# 1u_panel.net
KiCad netlist of a schematic drawn in EAGLE
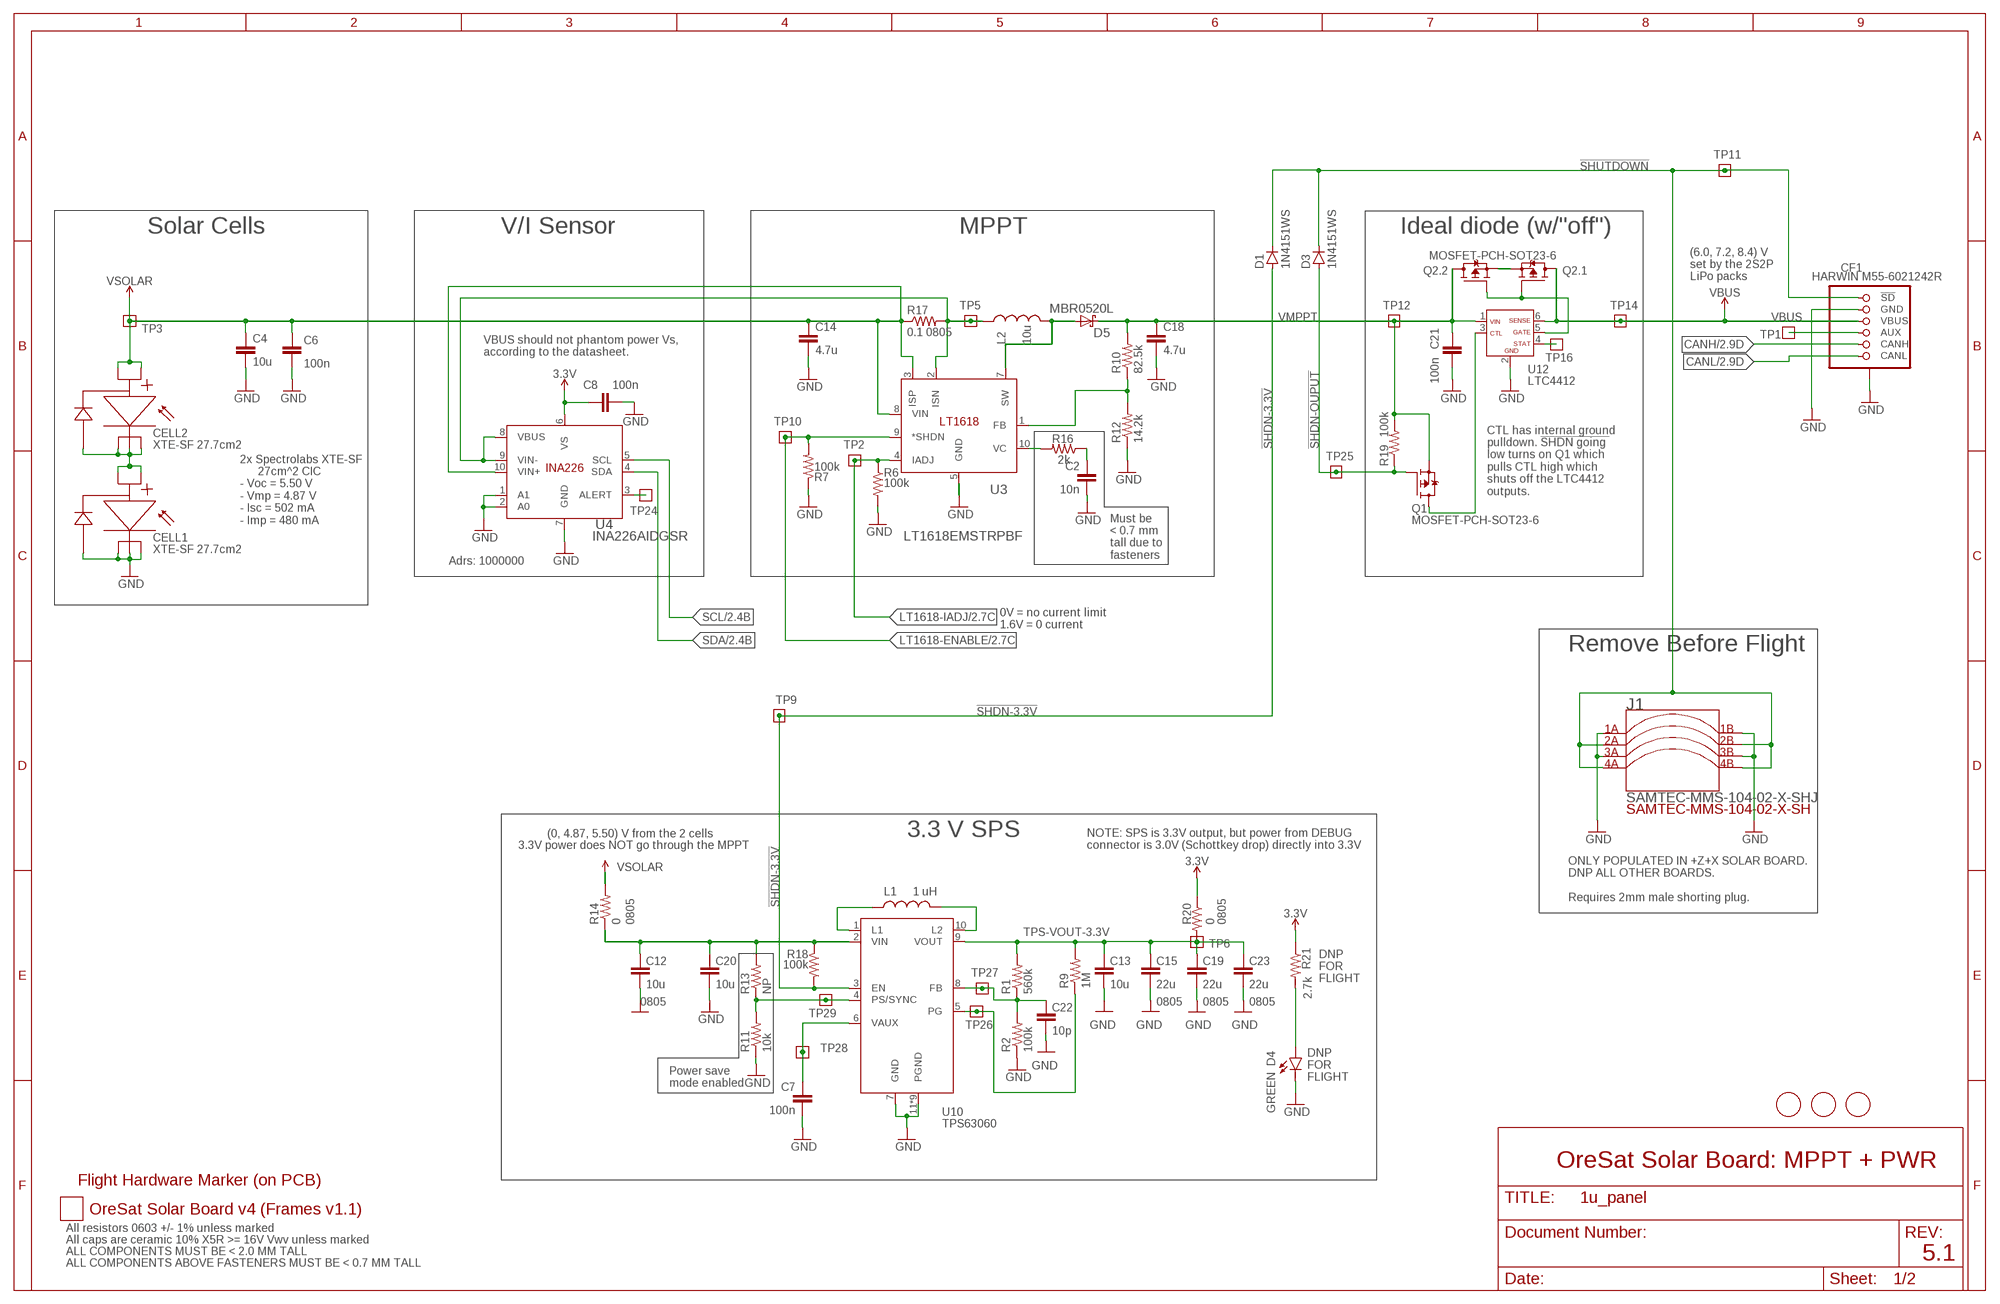
[diagram p0: schematic, sheet 1]
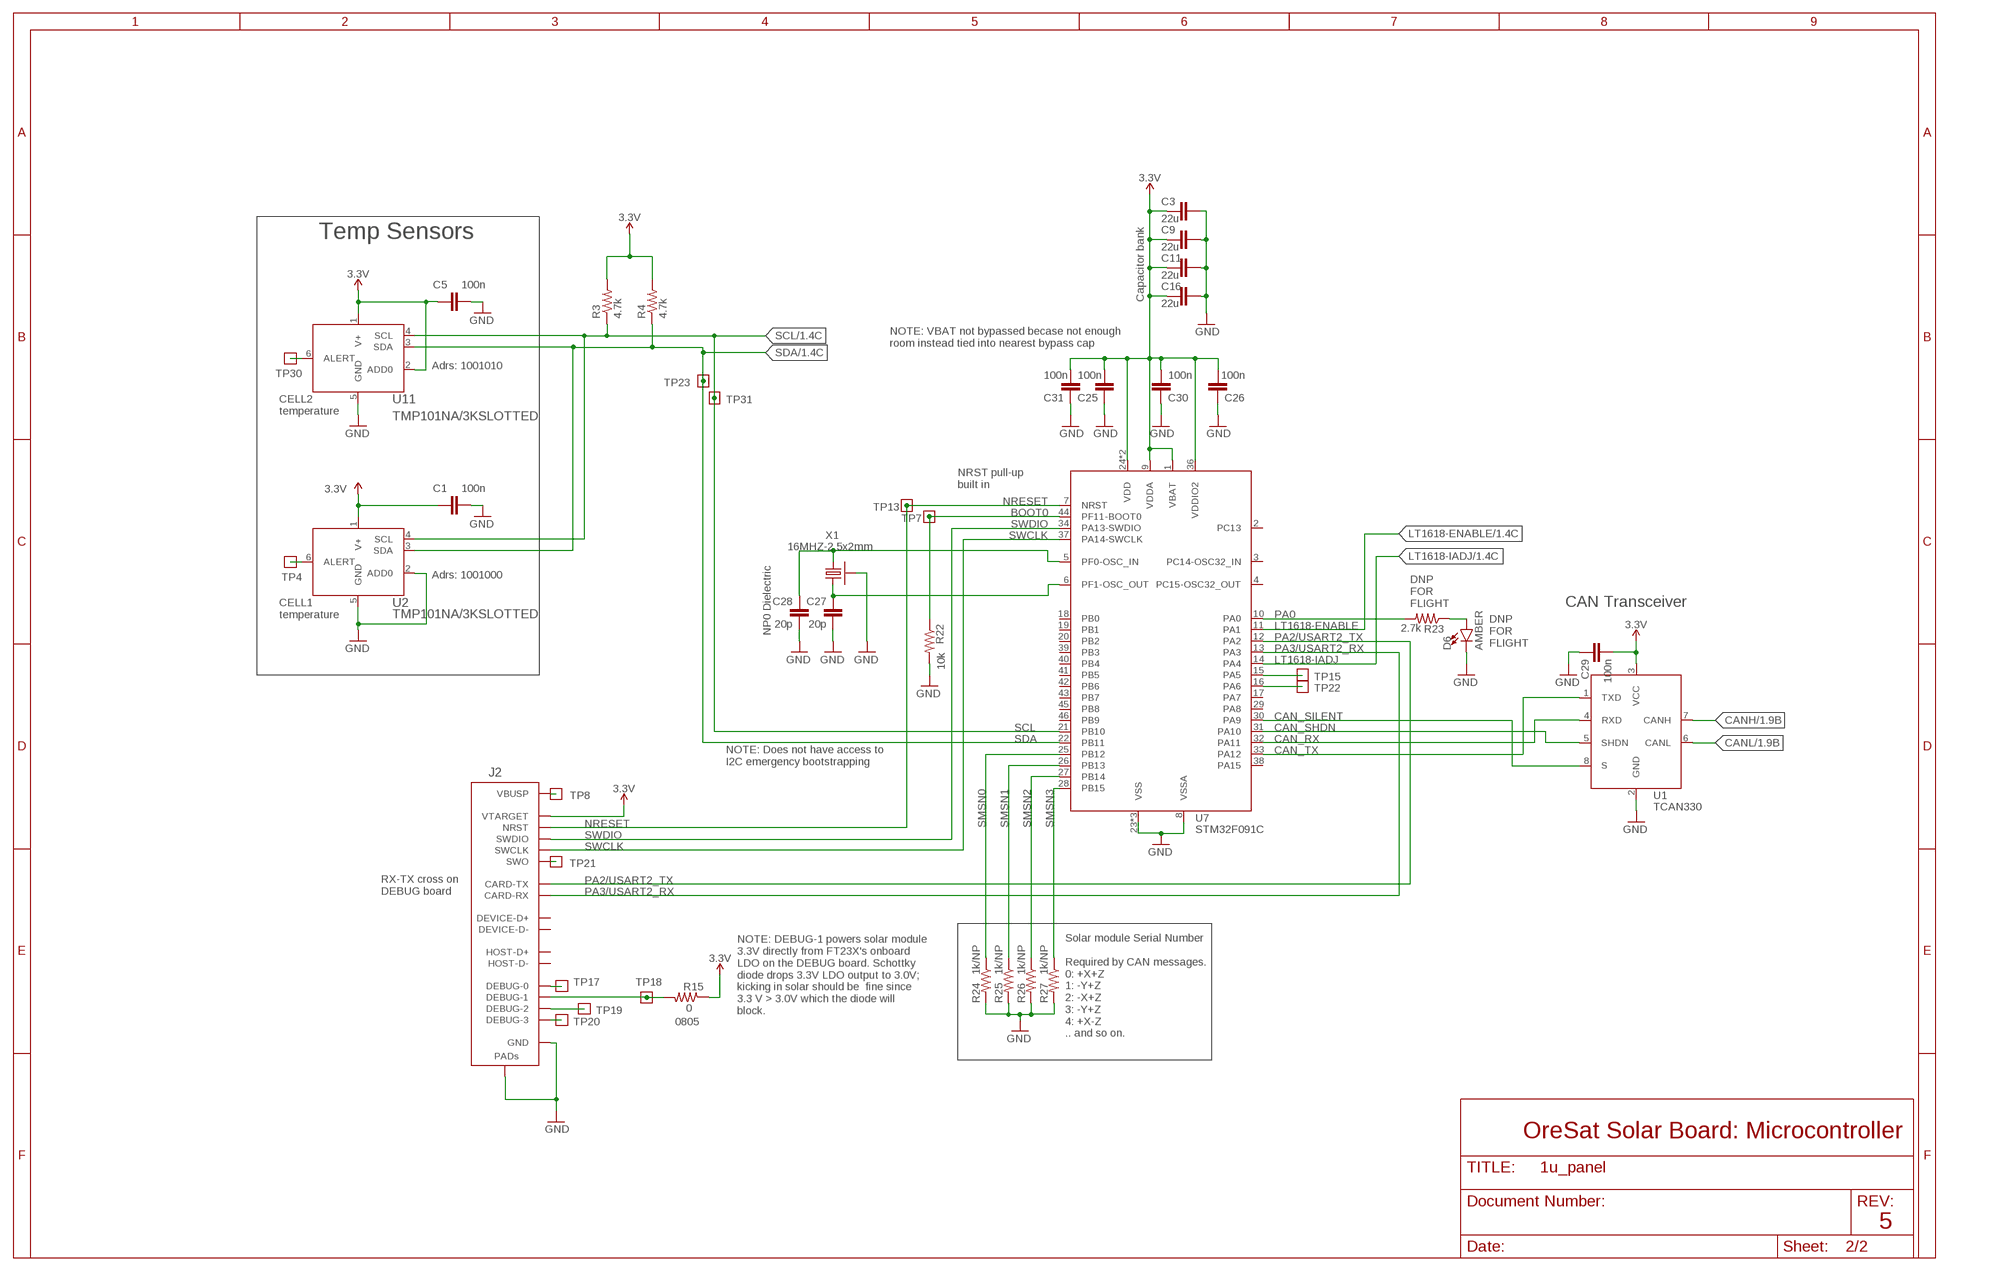
[diagram p1: schematic, sheet 2]

(export (version "E")
  (design (tool "Eeschema 10.0.6"))
  (components
    (comp (ref "C1")
      (value "100n")
      (footprint "eagle-import:.0603-C-NOSILK")
      (fields (field (name "MFR") "Kemet") (field (name "MPN") "CL10B104KB85PND"))
      (libsource (lib "eagle-import") (part "C-EU0603-C-NOSILK"))
    )
    (comp (ref "C3")
      (value "22u")
      (footprint "eagle-import:.0805-B-NOSILK")
      (fields (field (name "MFR") "Samsung") (field (name "MPN") "CL32B226KOJVPNE"))
      (libsource (lib "eagle-import") (part "C-EU0805-B-NOSILK"))
    )
    (comp (ref "C5")
      (value "100n")
      (footprint "eagle-import:.0603-C-NOSILK")
      (fields (field (name "MFR") "Kemet") (field (name "MPN") "CL10B104KB85PND"))
      (libsource (lib "eagle-import") (part "C-EU0603-C-NOSILK"))
    )
    (comp (ref "C9")
      (value "22u")
      (footprint "eagle-import:.0805-B-NOSILK")
      (fields (field (name "MFR") "Samsung") (field (name "MPN") "CL32B226KOJVPNE"))
      (libsource (lib "eagle-import") (part "C-EU0805-B-NOSILK"))
    )
    (comp (ref "C11")
      (value "22u")
      (footprint "eagle-import:.0805-B-NOSILK")
      (fields (field (name "MFR") "Samsung") (field (name "MPN") "CL32B226KOJVPNE"))
      (libsource (lib "eagle-import") (part "C-EU0805-B-NOSILK"))
    )
    (comp (ref "C16")
      (value "22u")
      (footprint "eagle-import:.0805-B-NOSILK")
      (fields (field (name "MFR") "Samsung") (field (name "MPN") "CL32B226KOJVPNE"))
      (libsource (lib "eagle-import") (part "C-EU0805-B-NOSILK"))
    )
    (comp (ref "C25")
      (value "100n")
      (footprint "eagle-import:.0603-C-NOSILK")
      (fields (field (name "MFR") "Kemet") (field (name "MPN") "CL10B104KB85PND"))
      (libsource (lib "eagle-import") (part "C-EU0603-C-NOSILK"))
    )
    (comp (ref "C26")
      (value "100n")
      (footprint "eagle-import:.0603-C-NOSILK")
      (fields (field (name "MFR") "Kemet") (field (name "MPN") "CL10B104KB85PND"))
      (libsource (lib "eagle-import") (part "C-EU0603-C-NOSILK"))
    )
    (comp (ref "C27")
      (value "20p")
      (footprint "eagle-import:.0603-C-NOSILK")
      (fields (field (name "MFR") "Murata") (field (name "MPN") "GCM1885C2A200JA16D"))
      (libsource (lib "eagle-import") (part "C-EU0603-C-NOSILK"))
    )
    (comp (ref "C28")
      (value "20p")
      (footprint "eagle-import:.0603-C-NOSILK")
      (fields (field (name "MFR") "Murata") (field (name "MPN") "GCM1885C2A200JA16D"))
      (libsource (lib "eagle-import") (part "C-EU0603-C-NOSILK"))
    )
    (comp (ref "C29")
      (value "100n")
      (footprint "eagle-import:.0603-C-NOSILK")
      (fields (field (name "MFR") "Kemet") (field (name "MPN") "CL10B104KB85PND"))
      (libsource (lib "eagle-import") (part "C-EU0603-C-NOSILK"))
    )
    (comp (ref "C30")
      (value "100n")
      (footprint "eagle-import:.0603-C-NOSILK")
      (fields (field (name "MFR") "Kemet") (field (name "MPN") "CL10B104KB85PND"))
      (libsource (lib "eagle-import") (part "C-EU0603-C-NOSILK"))
    )
    (comp (ref "C31")
      (value "100n")
      (footprint "eagle-import:.0603-C-NOSILK")
      (fields (field (name "MFR") "Kemet") (field (name "MPN") "CL10B104KB85PND"))
      (libsource (lib "eagle-import") (part "C-EU0603-C-NOSILK"))
    )
    (comp (ref "D6")
      (value "AMBER")
      (footprint "eagle-import:LED-0603")
      (fields (field (name "MFR") "Inolux") (field (name "MPN") "IN-S63AT5A"))
      (libsource (lib "eagle-import") (part "LED-GREEN0603"))
    )
    (comp (ref "J2")
      (value "ORESAT-DEBUG-CONNECTOR-ALL")
      (footprint "eagle-import:TE_2-1734592-0")
      (fields (field (name "MFR") "Wurth") (field (name "MPN") "687120183622  "))
      (libsource (lib "eagle-import") (part "ORESAT-DEBUG-CONNECTOR-ALL"))
    )
    (comp (ref "R3")
      (value "4.7k")
      (footprint "eagle-import:.0603-C-NOSILK")
      (fields (field (name "MFR") "Yageo") (field (name "MPN") "RE0603FRE074K7L"))
      (libsource (lib "eagle-import") (part "R-US_0603-C-NOSILK"))
    )
    (comp (ref "R4")
      (value "4.7k")
      (footprint "eagle-import:.0603-C-NOSILK")
      (fields (field (name "MFR") "Yageo") (field (name "MPN") "RE0603FRE074K7L"))
      (libsource (lib "eagle-import") (part "R-US_0603-C-NOSILK"))
    )
    (comp (ref "R15")
      (value "0")
      (footprint "eagle-import:.0805-C-NOSILK")
      (fields (field (name "MFR") "Stackpole") (field (name "MPN") "RMCF0805ZT0R00"))
      (libsource (lib "eagle-import") (part "R-US_0805-C-NOSILK"))
    )
    (comp (ref "R22")
      (value "10k")
      (footprint "eagle-import:.0603-C-NOSILK")
      (fields (field (name "MFR") "TE") (field (name "MPN") "CRGCQ0603F2K7"))
      (libsource (lib "eagle-import") (part "R-US_0603-C-NOSILK"))
    )
    (comp (ref "R23")
      (value "2.7k")
      (footprint "eagle-import:.0603-C-NOSILK")
      (fields (field (name "MFR") "TE") (field (name "MPN") "CRGCQ0603F2K7"))
      (libsource (lib "eagle-import") (part "R-US_0603-C-NOSILK"))
    )
    (comp (ref "R24")
      (value "1k/NP")
      (footprint "eagle-import:.0603-C-NOSILK")
      (fields (field (name "MFR") "Bourns") (field (name "MPN") "CR0603AFX-1001ELF"))
      (libsource (lib "eagle-import") (part "R-US_0603-C-NOSILK"))
    )
    (comp (ref "R25")
      (value "1k/NP")
      (footprint "eagle-import:.0603-C-NOSILK")
      (fields (field (name "MFR") "Bourns") (field (name "MPN") "CR0603AFX-1001ELF"))
      (libsource (lib "eagle-import") (part "R-US_0603-C-NOSILK"))
    )
    (comp (ref "R26")
      (value "1k/NP")
      (footprint "eagle-import:.0603-C-NOSILK")
      (fields (field (name "MFR") "Bourns") (field (name "MPN") "CR0603AFX-1001ELF"))
      (libsource (lib "eagle-import") (part "R-US_0603-C-NOSILK"))
    )
    (comp (ref "R27")
      (value "1k/NP")
      (footprint "eagle-import:.0603-C-NOSILK")
      (fields (field (name "MFR") "Bourns") (field (name "MPN") "CR0603AFX-1001ELF"))
      (libsource (lib "eagle-import") (part "R-US_0603-C-NOSILK"))
    )
    (comp (ref "TP4")
      (value "TEST-POINT-LARGE-SQUARE")
      (footprint "eagle-import:1X01")
      (libsource (lib "eagle-import") (part "TEST-POINT-LARGE-SQUARE"))
    )
    (comp (ref "TP7")
      (value "TEST-POINT-LARGE-SQUARE")
      (footprint "eagle-import:1X01")
      (libsource (lib "eagle-import") (part "TEST-POINT-LARGE-SQUARE"))
    )
    (comp (ref "TP8")
      (value "TEST-POINT-LARGE-SQUARE")
      (footprint "eagle-import:1X01")
      (libsource (lib "eagle-import") (part "TEST-POINT-LARGE-SQUARE"))
    )
    (comp (ref "TP13")
      (value "TEST-POINT-LARGE-SQUARE")
      (footprint "eagle-import:1X01")
      (libsource (lib "eagle-import") (part "TEST-POINT-LARGE-SQUARE"))
    )
    (comp (ref "TP15")
      (value "TEST-POINT-LARGE-SQUARE")
      (footprint "eagle-import:1X01")
      (libsource (lib "eagle-import") (part "TEST-POINT-LARGE-SQUARE"))
    )
    (comp (ref "TP17")
      (value "TEST-POINT-LARGE-SQUARE")
      (footprint "eagle-import:1X01")
      (libsource (lib "eagle-import") (part "TEST-POINT-LARGE-SQUARE"))
    )
    (comp (ref "TP18")
      (value "TEST-POINT-LARGE-SQUARE")
      (footprint "eagle-import:1X01")
      (libsource (lib "eagle-import") (part "TEST-POINT-LARGE-SQUARE"))
    )
    (comp (ref "TP19")
      (value "TEST-POINT-LARGE-SQUARE")
      (footprint "eagle-import:1X01")
      (libsource (lib "eagle-import") (part "TEST-POINT-LARGE-SQUARE"))
    )
    (comp (ref "TP20")
      (value "TEST-POINT-LARGE-SQUARE")
      (footprint "eagle-import:1X01")
      (libsource (lib "eagle-import") (part "TEST-POINT-LARGE-SQUARE"))
    )
    (comp (ref "TP21")
      (value "TEST-POINT-LARGE-SQUARE")
      (footprint "eagle-import:1X01")
      (libsource (lib "eagle-import") (part "TEST-POINT-LARGE-SQUARE"))
    )
    (comp (ref "TP22")
      (value "TEST-POINT-LARGE-SQUARE")
      (footprint "eagle-import:1X01")
      (libsource (lib "eagle-import") (part "TEST-POINT-LARGE-SQUARE"))
    )
    (comp (ref "TP23")
      (value "TEST-POINT-LARGE-SQUARE")
      (footprint "eagle-import:1X01")
      (libsource (lib "eagle-import") (part "TEST-POINT-LARGE-SQUARE"))
    )
    (comp (ref "TP30")
      (value "TEST-POINT-LARGE-SQUARE")
      (footprint "eagle-import:1X01")
      (libsource (lib "eagle-import") (part "TEST-POINT-LARGE-SQUARE"))
    )
    (comp (ref "TP31")
      (value "TEST-POINT-LARGE-SQUARE")
      (footprint "eagle-import:1X01")
      (libsource (lib "eagle-import") (part "TEST-POINT-LARGE-SQUARE"))
    )
    (comp (ref "U1")
      (value "TCAN330")
      (footprint "eagle-import:SOT23-8_TI-DCN")
      (fields (field (name "MFR") "Texas Instruments") (field (name "MPN") "TCAN330GDCNT"))
      (libsource (lib "eagle-import") (part "TCAN330"))
    )
    (comp (ref "U2")
      (value "TMP101NA/3KSLOTTED")
      (footprint "eagle-import:DBV6-SLOT")
      (fields (field (name "MFR") "Texas Instruments") (field (name "MPN") "TMP101NA/3K"))
      (libsource (lib "eagle-import") (part "TMP101NA/3KSLOTTED"))
    )
    (comp (ref "U7")
      (value "STM32F091C")
      (footprint "eagle-import:STM32F091C")
      (fields (field (name "MFR") "STMicroelectronics") (field (name "MPN") "STM32F091CCT6TR"))
      (libsource (lib "eagle-import") (part "STM32F091C"))
    )
    (comp (ref "U11")
      (value "TMP101NA/3KSLOTTED")
      (footprint "eagle-import:DBV6-SLOT")
      (fields (field (name "MFR") "Texas Instruments") (field (name "MPN") "TMP101NA/3K"))
      (libsource (lib "eagle-import") (part "TMP101NA/3KSLOTTED"))
    )
    (comp (ref "X1")
      (value "16MHZ-2.5x2mm")
      (footprint "eagle-import:CRYSTAL_2.5X2")
      (fields (field (name "MFR") "ECS Inc.") (field (name "MPN") "ECS-160-10-36Q-ES-TR"))
      (libsource (lib "eagle-import") (part "CRYSTAL-WITH-GND"))
    )
    (comp (ref "C2")
      (value "10n")
      (footprint "eagle-import:.0603-C-NOSILK")
      (fields (field (name "MFR") "Taiyo") (field (name "MPN") "UMK107B7103KAHT"))
      (libsource (lib "eagle-import") (part "C-EU0603-C-NOSILK"))
    )
    (comp (ref "C4")
      (value "10u")
      (footprint "eagle-import:.0603-C-NOSILK")
      (fields (field (name "MFR") "Murata") (field (name "MPN") "GRT188R61C106KE13D"))
      (libsource (lib "eagle-import") (part "C-EU0603-C-NOSILK"))
    )
    (comp (ref "C6")
      (value "100n")
      (footprint "eagle-import:.0603-C-NOSILK")
      (fields (field (name "MFR") "Kemet") (field (name "MPN") "CL10B104KB85PND"))
      (libsource (lib "eagle-import") (part "C-EU0603-C-NOSILK"))
    )
    (comp (ref "C7")
      (value "100n")
      (footprint "eagle-import:.0603-C-NOSILK")
      (fields (field (name "MFR") "Kemet") (field (name "MPN") "CL10B104KB85PND"))
      (libsource (lib "eagle-import") (part "C-EU0603-C-NOSILK"))
    )
    (comp (ref "C8")
      (value "100n")
      (footprint "eagle-import:.0603-C-NOSILK")
      (fields (field (name "MFR") "Kemet") (field (name "MPN") "CL10B104KB85PND"))
      (libsource (lib "eagle-import") (part "C-EU0603-C-NOSILK"))
    )
    (comp (ref "C12")
      (value "10u")
      (footprint "eagle-import:.0805-B-NOSILK")
      (fields (field (name "MFR") "Murata") (field (name "MPN") "GRT21BR61C106KE01L"))
      (libsource (lib "eagle-import") (part "C-EU0805-B-NOSILK"))
    )
    (comp (ref "C13")
      (value "10u")
      (footprint "eagle-import:.0603-C-NOSILK")
      (fields (field (name "MFR") "Murata") (field (name "MPN") "GRT188R61C106KE13D"))
      (libsource (lib "eagle-import") (part "C-EU0603-C-NOSILK"))
    )
    (comp (ref "C14")
      (value "4.7u")
      (footprint "eagle-import:.0603-C-NOSILK")
      (fields (field (name "MFR") "Taiyo") (field (name "MPN") "EMK107BBJ475KAHT"))
      (libsource (lib "eagle-import") (part "C-EU0603-C-NOSILK"))
    )
    (comp (ref "C15")
      (value "22u")
      (footprint "eagle-import:.0805-B-NOSILK")
      (fields (field (name "MFR") "Samsung") (field (name "MPN") "CL32B226KOJVPNE"))
      (libsource (lib "eagle-import") (part "C-EU0805-B-NOSILK"))
    )
    (comp (ref "C18")
      (value "4.7u")
      (footprint "eagle-import:.0603-C-NOSILK")
      (fields (field (name "MFR") "Taiyo") (field (name "MPN") "EMK107BBJ475KAHT"))
      (libsource (lib "eagle-import") (part "C-EU0603-C-NOSILK"))
    )
    (comp (ref "C19")
      (value "22u")
      (footprint "eagle-import:.0805-B-NOSILK")
      (fields (field (name "MFR") "Samsung") (field (name "MPN") "CL32B226KOJVPNE"))
      (libsource (lib "eagle-import") (part "C-EU0805-B-NOSILK"))
    )
    (comp (ref "C20")
      (value "10u")
      (footprint "eagle-import:.0603-C-NOSILK")
      (fields (field (name "MFR") "Murata") (field (name "MPN") "GRT188R61C106KE13D"))
      (libsource (lib "eagle-import") (part "C-EU0603-C-NOSILK"))
    )
    (comp (ref "C21")
      (value "100n")
      (footprint "eagle-import:.0402-B-NOSILK")
      (fields (field (name "MFR") "Kemet") (field (name "MPN") "CL10B104KB85PND"))
      (libsource (lib "eagle-import") (part "rcl_custom_C-EU0402-B-NOSILK"))
    )
    (comp (ref "C22")
      (value "10p")
      (footprint "eagle-import:.0603-C-NOSILK")
      (fields (field (name "MFR") "Murata") (field (name "MPN") "GRT188R61C106KE13D"))
      (libsource (lib "eagle-import") (part "C-EU0603-C-NOSILK"))
    )
    (comp (ref "C23")
      (value "22u")
      (footprint "eagle-import:.0805-B-NOSILK")
      (fields (field (name "MFR") "Samsung") (field (name "MPN") "CL32B226KOJVPNE"))
      (libsource (lib "eagle-import") (part "C-EU0805-B-NOSILK"))
    )
    (comp (ref "CELL1")
      (value "XTE-SF 27.7cm2")
      (footprint "eagle-import:SPECTROLAB-XTE-SF")
      (libsource (lib "eagle-import") (part "SPECTROLAB-XTE-SF"))
    )
    (comp (ref "CELL2")
      (value "XTE-SF 27.7cm2")
      (footprint "eagle-import:SPECTROLAB-XTE-SF")
      (libsource (lib "eagle-import") (part "SPECTROLAB-XTE-SF"))
    )
    (comp (ref "CF1")
      (value "HARWIN M55-6021242R")
      (footprint "eagle-import:HARWIN-M55-60X1242R")
      (fields (field (name "MFR") "HARWIN") (field (name "MPN") "M55-6021242R"))
      (libsource (lib "eagle-import") (part "SOLAR-BOARD-CONNECTOR"))
    )
    (comp (ref "D1")
      (value "1N4151WS")
      (footprint "eagle-import:SOD323-R")
      (libsource (lib "eagle-import") (part "DIODE-SOD323-R"))
    )
    (comp (ref "D3")
      (value "1N4151WS")
      (footprint "eagle-import:SOD323-R")
      (libsource (lib "eagle-import") (part "DIODE-SOD323-R"))
    )
    (comp (ref "D4")
      (value "GREEN")
      (footprint "eagle-import:LED-0603")
      (fields (field (name "MFR") "Inolux") (field (name "MPN") "IN-S63AT5A"))
      (libsource (lib "eagle-import") (part "LED-GREEN0603"))
    )
    (comp (ref "D5")
      (value "MBR0520L")
      (footprint "eagle-import:SOD123")
      (fields (field (name "MFR") "OnSemi") (field (name "MPN") "NRVB130T3G"))
      (libsource (lib "eagle-import") (part "NRVB130TGSOD123"))
    )
    (comp (ref "J1")
      (value "SAMTEC-MMS-104-02-X-SHJ")
      (footprint "eagle-import:SAMTEC-MMS-104-02-X-SH")
      (libsource (lib "eagle-import") (part "SAMTEC-MMS-104-02-X-SHJ"))
    )
    (comp (ref "L1")
      (value "1 uH")
      (footprint "eagle-import:IND_1226AS-H-1R0N=P2")
      (fields (field (name "MFR") "TDK") (field (name "MPN") "VLS3010CX-1R5M-1"))
      (libsource (lib "eagle-import") (part "L-MURATA-1226AS-H-1R0N=P2"))
    )
    (comp (ref "L2")
      (value "10u")
      (footprint "eagle-import:NONSTANDARD")
      (fields (field (name "MFR") "WURTH") (field (name "MPN") "744042100"))
      (libsource (lib "eagle-import") (part "L-WURTH-744042100"))
    )
    (comp (ref "PCB1")
      (value "ORESAT-SOLAR-BOARD-V4-SPECTROLABS")
      (footprint "eagle-import:ORESAT-SOLAR-BOARD-V4")
      (libsource (lib "eagle-import") (part "ORESAT-SOLAR-BOARD-V4-SPECTROLABS"))
    )
    (comp (ref "Q1")
      (value "MOSFET-PCH-SOT23-6")
      (footprint "eagle-import:SOT23-6")
      (fields (field (name "MFR") "Diodes Inc.") (field (name "MPN") "DMP3050LVT-7"))
      (libsource (lib "eagle-import") (part "MOSFET-PCH-SOT23-6"))
    )
    (comp (ref "Q2")
      (value "MOSFET-PCH-SOT23-6")
      (footprint "eagle-import:SOT23-6")
      (fields
        (field (name "MFR") "Diodes Inc.")
        (field (name "MPN") "DMP2240UDM-7")
        (field (name "DIS") "Digi-Key")
        (field (name "DPN") "DMP2240UDMDICT-ND")
      )
      (libsource (lib "eagle-import") (part "Q-MOSFET-PCH-dual-SOT23-6_MOSFET-PCH-SOT23-6"))
    )
    (comp (ref "R1")
      (value "560k")
      (footprint "eagle-import:.0603-C-NOSILK")
      (fields (field (name "MFR") "TE") (field (name "MPN") "CRGCQ0603F470K"))
      (libsource (lib "eagle-import") (part "R-US_0603-C-NOSILK"))
    )
    (comp (ref "R2")
      (value "100k")
      (footprint "eagle-import:.0603-C-NOSILK")
      (fields (field (name "MFR") "Susumu") (field (name "MPN") "RR0816P-104-D"))
      (libsource (lib "eagle-import") (part "R-US_0603-C-NOSILK"))
    )
    (comp (ref "R6")
      (value "100k")
      (footprint "eagle-import:.0603-C-NOSILK")
      (fields (field (name "MFR") "Stackpole") (field (name "MPN") "RNCP0603FTD10K0"))
      (libsource (lib "eagle-import") (part "R-US_0603-C-NOSILK"))
    )
    (comp (ref "R7")
      (value "100k")
      (footprint "eagle-import:.0603-C-NOSILK")
      (fields (field (name "MFR") "Stackpole") (field (name "MPN") "RNCP0603FTD10K0"))
      (libsource (lib "eagle-import") (part "R-US_0603-C-NOSILK"))
    )
    (comp (ref "R9")
      (value "1M")
      (footprint "eagle-import:.0603-C-NOSILK")
      (libsource (lib "eagle-import") (part "R-US_0603-C-NOSILK"))
    )
    (comp (ref "R10")
      (value "82.5k")
      (footprint "eagle-import:.0603-C-NOSILK")
      (fields (field (name "MFR") "Panasonic") (field (name "MPN") "ERA-3AEB8252V"))
      (libsource (lib "eagle-import") (part "R-US_0603-C-NOSILK"))
    )
    (comp (ref "R11")
      (value "10k")
      (footprint "eagle-import:.0603-C-NOSILK")
      (libsource (lib "eagle-import") (part "R-US_0603-C-NOSILK"))
    )
    (comp (ref "R12")
      (value "14.2k")
      (footprint "eagle-import:.0603-C-NOSILK")
      (fields (field (name "MFR") "KOA") (field (name "MPN") "RN73R1JTTD1422D25"))
      (libsource (lib "eagle-import") (part "R-US_0603-C-NOSILK"))
    )
    (comp (ref "R13")
      (value "NP")
      (footprint "eagle-import:.0603-C-NOSILK")
      (fields (field (name "MFR") "Stackpole") (field (name "MPN") "RNCP0603FTD10K0"))
      (libsource (lib "eagle-import") (part "R-US_0603-C-NOSILK"))
    )
    (comp (ref "R14")
      (value "0")
      (footprint "eagle-import:.0805-C-NOSILK")
      (fields (field (name "MFR") "Stackpole") (field (name "MPN") "RMCF0805ZT0R00"))
      (libsource (lib "eagle-import") (part "R-US_0805-C-NOSILK"))
    )
    (comp (ref "R16")
      (value "2k")
      (footprint "eagle-import:.0603-C-NOSILK")
      (fields (field (name "MFR") "KOA") (field (name "MPN") "RK73H1JTTD2001F"))
      (libsource (lib "eagle-import") (part "R-US_0603-C-NOSILK"))
    )
    (comp (ref "R17")
      (value "0.1 0805")
      (footprint "eagle-import:.0805-C-NOSILK")
      (fields (field (name "MFR") "Stackpole") (field (name "MPN") "RMCF0805ZT0R00"))
      (libsource (lib "eagle-import") (part "R-US_0805-C-NOSILK"))
    )
    (comp (ref "R18")
      (value "100k")
      (footprint "eagle-import:.0603-C-NOSILK")
      (fields (field (name "MFR") "Stackpole") (field (name "MPN") "RNCP0603FTD10K0"))
      (libsource (lib "eagle-import") (part "R-US_0603-C-NOSILK"))
    )
    (comp (ref "R19")
      (value "100k")
      (footprint "eagle-import:.0603-C-NOSILK")
      (fields (field (name "MFR") "Stackpole") (field (name "MPN") "RNCP0603FTD10K0"))
      (libsource (lib "eagle-import") (part "R-US_0603-C-NOSILK"))
    )
    (comp (ref "R20")
      (value "0")
      (footprint "eagle-import:.0805-C-NOSILK")
      (fields (field (name "MFR") "Stackpole") (field (name "MPN") "RMCF0805ZT0R00"))
      (libsource (lib "eagle-import") (part "R-US_0805-C-NOSILK"))
    )
    (comp (ref "R21")
      (value "2.7k")
      (footprint "eagle-import:.0603-C-NOSILK")
      (fields (field (name "MFR") "TE") (field (name "MPN") "CRGCQ0603F2K7"))
      (libsource (lib "eagle-import") (part "R-US_0603-C-NOSILK"))
    )
    (comp (ref "TP1")
      (value "TEST-POINT-LARGE-SQUARE")
      (footprint "eagle-import:1X01")
      (libsource (lib "eagle-import") (part "TEST-POINT-LARGE-SQUARE"))
    )
    (comp (ref "TP2")
      (value "TEST-POINT-LARGE-SQUARE")
      (footprint "eagle-import:1X01")
      (libsource (lib "eagle-import") (part "TEST-POINT-LARGE-SQUARE"))
    )
    (comp (ref "TP3")
      (value "TEST-POINT-LARGE-SQUARE")
      (footprint "eagle-import:1X01")
      (libsource (lib "eagle-import") (part "TEST-POINT-LARGE-SQUARE"))
    )
    (comp (ref "TP5")
      (value "TEST-POINT-LARGE-SQUARE")
      (footprint "eagle-import:1X01")
      (libsource (lib "eagle-import") (part "TEST-POINT-LARGE-SQUARE"))
    )
    (comp (ref "TP6")
      (value "TEST-POINT-LARGE-SQUARE")
      (footprint "eagle-import:1X01")
      (libsource (lib "eagle-import") (part "TEST-POINT-LARGE-SQUARE"))
    )
    (comp (ref "TP9")
      (value "TEST-POINT-LARGE-SQUARE")
      (footprint "eagle-import:1X01")
      (libsource (lib "eagle-import") (part "TEST-POINT-LARGE-SQUARE"))
    )
    (comp (ref "TP10")
      (value "TEST-POINT-LARGE-SQUARE")
      (footprint "eagle-import:1X01")
      (libsource (lib "eagle-import") (part "TEST-POINT-LARGE-SQUARE"))
    )
    (comp (ref "TP11")
      (value "TEST-POINT-LARGE-SQUARE")
      (footprint "eagle-import:1X01")
      (libsource (lib "eagle-import") (part "TEST-POINT-LARGE-SQUARE"))
    )
    (comp (ref "TP12")
      (value "TEST-POINT-LARGE-SQUARE")
      (footprint "eagle-import:1X01")
      (libsource (lib "eagle-import") (part "TEST-POINT-LARGE-SQUARE"))
    )
    (comp (ref "TP14")
      (value "TEST-POINT-LARGE-SQUARE")
      (footprint "eagle-import:1X01")
      (libsource (lib "eagle-import") (part "TEST-POINT-LARGE-SQUARE"))
    )
    (comp (ref "TP16")
      (value "TEST-POINT-LARGE-SQUARE")
      (footprint "eagle-import:1X01")
      (libsource (lib "eagle-import") (part "TEST-POINT-LARGE-SQUARE"))
    )
    (comp (ref "TP24")
      (value "TEST-POINT-LARGE-SQUARE")
      (footprint "eagle-import:1X01")
      (libsource (lib "eagle-import") (part "TEST-POINT-LARGE-SQUARE"))
    )
    (comp (ref "TP25")
      (value "TEST-POINT-LARGE-SQUARE")
      (footprint "eagle-import:1X01")
      (libsource (lib "eagle-import") (part "TEST-POINT-LARGE-SQUARE"))
    )
    (comp (ref "TP26")
      (value "TEST-POINT-LARGE-SQUARE")
      (footprint "eagle-import:1X01")
      (libsource (lib "eagle-import") (part "TEST-POINT-LARGE-SQUARE"))
    )
    (comp (ref "TP27")
      (value "TEST-POINT-LARGE-SQUARE")
      (footprint "eagle-import:1X01")
      (libsource (lib "eagle-import") (part "TEST-POINT-LARGE-SQUARE"))
    )
    (comp (ref "TP28")
      (value "TEST-POINT-LARGE-SQUARE")
      (footprint "eagle-import:1X01")
      (libsource (lib "eagle-import") (part "TEST-POINT-LARGE-SQUARE"))
    )
    (comp (ref "TP29")
      (value "TEST-POINT-LARGE-SQUARE")
      (footprint "eagle-import:1X01")
      (libsource (lib "eagle-import") (part "TEST-POINT-LARGE-SQUARE"))
    )
    (comp (ref "U$1")
      (value "FLIGHMARKERNEW")
      (footprint "eagle-import:FLIGHTMARKER_NEW_BOARDS")
      (libsource (lib "eagle-import") (part "FLIGHMARKERNEW"))
    )
    (comp (ref "U$2")
      (value "FIDUCIAL")
      (footprint "eagle-import:FIDUCIAL_1MM")
      (libsource (lib "eagle-import") (part "FIDUCIAL"))
    )
    (comp (ref "U$3")
      (value "FIDUCIAL")
      (footprint "eagle-import:FIDUCIAL_1MM")
      (libsource (lib "eagle-import") (part "FIDUCIAL"))
    )
    (comp (ref "U$4")
      (value "FIDUCIAL")
      (footprint "eagle-import:FIDUCIAL_1MM")
      (libsource (lib "eagle-import") (part "FIDUCIAL"))
    )
    (comp (ref "U3")
      (value "LT1618EMSTRPBF")
      (footprint "eagle-import:MSOP-10_MS")
      (fields
        (field (name "DIGI-KEY_PART_NUMBER") "LT1618EMS#TRPBFCT-ND")
        (field (name "MF") "Linear Technology/Analog")
        (field (name "MP") "LT1618EMS#TRPBF")
      )
      (libsource (lib "eagle-import") (part "LT1618EMSTRPBF"))
    )
    (comp (ref "U4")
      (value "INA226AIDGSR")
      (footprint "eagle-import:DGS10")
      (fields (field (name "MFR") "TI"))
      (libsource (lib "eagle-import") (part "INA226AIDGSR"))
    )
    (comp (ref "U10")
      (value "TPS63060")
      (footprint "eagle-import:CONV_TPS63060DSCT")
      (libsource (lib "eagle-import") (part "U-TI-TPS63060DCT-BUCKBOOST"))
    )
    (comp (ref "U12")
      (value "LTC4412")
      (footprint "eagle-import:SOT23-6")
      (fields (field (name "MFR") "Linear Technologies") (field (name "MPN") "LTC4412ES6#TRPBF"))
      (libsource (lib "eagle-import") (part "LTC4412"))
    )
  )
  (nets
    (net (code "1") (name "3.3V") (class "Default")
      (node (ref "C1") (pin "1") (pinfunction "1_1") (pintype "passive"))
      (node (ref "C11") (pin "1") (pinfunction "1_1") (pintype "passive"))
      (node (ref "C16") (pin "1") (pinfunction "1_1") (pintype "passive"))
      (node (ref "C25") (pin "2") (pinfunction "2_2") (pintype "passive"))
      (node (ref "C26") (pin "2") (pinfunction "2_2") (pintype "passive"))
      (node (ref "C29") (pin "2") (pinfunction "2_2") (pintype "passive"))
      (node (ref "C3") (pin "1") (pinfunction "1_1") (pintype "passive"))
      (node (ref "C30") (pin "2") (pinfunction "2_2") (pintype "passive"))
      (node (ref "C31") (pin "2") (pinfunction "2_2") (pintype "passive"))
      (node (ref "C5") (pin "1") (pinfunction "1_1") (pintype "passive"))
      (node (ref "C8") (pin "1") (pinfunction "1_1") (pintype "passive"))
      (node (ref "C9") (pin "1") (pinfunction "1_1") (pintype "passive"))
      (node (ref "J2") (pin "11") (pinfunction "VTARGET_11") (pintype "passive"))
      (node (ref "R15") (pin "1") (pinfunction "1_1") (pintype "passive"))
      (node (ref "R20") (pin "1") (pinfunction "1_1") (pintype "passive"))
      (node (ref "R21") (pin "1") (pinfunction "1_1") (pintype "passive"))
      (node (ref "R3") (pin "2") (pinfunction "2_2") (pintype "passive"))
      (node (ref "R4") (pin "2") (pinfunction "2_2") (pintype "passive"))
      (node (ref "U1") (pin "3") (pinfunction "VCC_3") (pintype "power_in"))
      (node (ref "U11") (pin "1") (pinfunction "V+_1") (pintype "power_in"))
      (node (ref "U11") (pin "2") (pinfunction "ADD0_2") (pintype "input"))
      (node (ref "U2") (pin "1") (pinfunction "V+_1") (pintype "power_in"))
      (node (ref "U4") (pin "6") (pinfunction "VS_6") (pintype "power_in"))
      (node (ref "U7") (pin "1") (pinfunction "VBAT_1") (pintype "power_in"))
      (node (ref "U7") (pin "24") (pinfunction "VDD_24") (pintype "power_in"))
      (node (ref "U7") (pin "36") (pinfunction "VDDIO2_36") (pintype "power_in"))
      (node (ref "U7") (pin "48") (pinfunction "VDD_48") (pintype "power_in"))
      (node (ref "U7") (pin "9") (pinfunction "VDDA_9") (pintype "power_in"))
    )
    (net (code "2") (name "BOOT0") (class "Default")
      (node (ref "R22") (pin "1") (pinfunction "1_1") (pintype "passive"))
      (node (ref "TP7") (pin "1") (pinfunction "1_1") (pintype "passive"))
      (node (ref "U7") (pin "44") (pinfunction "PF11-BOOT0_44") (pintype "bidirectional"))
    )
    (net (code "3") (name "CANH") (class "Default")
      (node (ref "CF1") (pin "10") (pinfunction "CANH_10") (pintype "passive"))
      (node (ref "CF1") (pin "9") (pinfunction "CANH_9") (pintype "passive"))
      (node (ref "U1") (pin "7") (pinfunction "CANH_7") (pintype "bidirectional"))
    )
    (net (code "4") (name "CANL") (class "Default")
      (node (ref "CF1") (pin "11") (pinfunction "CANL_11") (pintype "passive"))
      (node (ref "CF1") (pin "12") (pinfunction "CANL_12") (pintype "passive"))
      (node (ref "U1") (pin "6") (pinfunction "CANL_6") (pintype "bidirectional"))
    )
    (net (code "5") (name "CAN_RX") (class "Default")
      (node (ref "U1") (pin "4") (pinfunction "RXD_4") (pintype "output"))
      (node (ref "U7") (pin "32") (pinfunction "PA11_32") (pintype "bidirectional"))
    )
    (net (code "6") (name "CAN_SHDN") (class "Default")
      (node (ref "U1") (pin "5") (pinfunction "SHDN_5") (pintype "input"))
      (node (ref "U7") (pin "31") (pinfunction "PA10_31") (pintype "bidirectional"))
    )
    (net (code "7") (name "CAN_SILENT") (class "Default")
      (node (ref "U1") (pin "8") (pinfunction "S_8") (pintype "input"))
      (node (ref "U7") (pin "30") (pinfunction "PA9_30") (pintype "bidirectional"))
    )
    (net (code "8") (name "CAN_TX") (class "Default")
      (node (ref "U1") (pin "1") (pinfunction "TXD_1") (pintype "input"))
      (node (ref "U7") (pin "33") (pinfunction "PA12_33") (pintype "bidirectional"))
    )
    (net (code "9") (name "GND") (class "Default")
      (node (ref "C1") (pin "2") (pinfunction "2_2") (pintype "passive"))
      (node (ref "C11") (pin "2") (pinfunction "2_2") (pintype "passive"))
      (node (ref "C12") (pin "2") (pinfunction "2_2") (pintype "passive"))
      (node (ref "C13") (pin "2") (pinfunction "2_2") (pintype "passive"))
      (node (ref "C14") (pin "2") (pinfunction "2_2") (pintype "passive"))
      (node (ref "C15") (pin "2") (pinfunction "2_2") (pintype "passive"))
      (node (ref "C16") (pin "2") (pinfunction "2_2") (pintype "passive"))
      (node (ref "C18") (pin "2") (pinfunction "2_2") (pintype "passive"))
      (node (ref "C19") (pin "2") (pinfunction "2_2") (pintype "passive"))
      (node (ref "C2") (pin "2") (pinfunction "2_2") (pintype "passive"))
      (node (ref "C20") (pin "2") (pinfunction "2_2") (pintype "passive"))
      (node (ref "C21") (pin "2") (pinfunction "2_2") (pintype "passive"))
      (node (ref "C22") (pin "2") (pinfunction "2_2") (pintype "passive"))
      (node (ref "C23") (pin "2") (pinfunction "2_2") (pintype "passive"))
      (node (ref "C25") (pin "1") (pinfunction "1_1") (pintype "passive"))
      (node (ref "C26") (pin "1") (pinfunction "1_1") (pintype "passive"))
      (node (ref "C27") (pin "2") (pinfunction "2_2") (pintype "passive"))
      (node (ref "C28") (pin "2") (pinfunction "2_2") (pintype "passive"))
      (node (ref "C29") (pin "1") (pinfunction "1_1") (pintype "passive"))
      (node (ref "C3") (pin "2") (pinfunction "2_2") (pintype "passive"))
      (node (ref "C30") (pin "1") (pinfunction "1_1") (pintype "passive"))
      (node (ref "C31") (pin "1") (pinfunction "1_1") (pintype "passive"))
      (node (ref "C4") (pin "2") (pinfunction "2_2") (pintype "passive"))
      (node (ref "C5") (pin "2") (pinfunction "2_2") (pintype "passive"))
      (node (ref "C6") (pin "2") (pinfunction "2_2") (pintype "passive"))
      (node (ref "C7") (pin "2") (pinfunction "2_2") (pintype "passive"))
      (node (ref "C8") (pin "2") (pinfunction "2_2") (pintype "passive"))
      (node (ref "C9") (pin "2") (pinfunction "2_2") (pintype "passive"))
      (node (ref "CELL1") (pin "NEG1") (pinfunction "C1_NEG1") (pintype "passive"))
      (node (ref "CELL1") (pin "NEG2") (pinfunction "C2_NEG2") (pintype "passive"))
      (node (ref "CELL1") (pin "NEG3") (pinfunction "C3_NEG3") (pintype "passive"))
      (node (ref "CELL1") (pin "NEG4") (pinfunction "C4_NEG4") (pintype "passive"))
      (node (ref "CF1") (pin "3") (pinfunction "GND_3") (pintype "passive"))
      (node (ref "CF1") (pin "4") (pinfunction "GND_4") (pintype "passive"))
      (node (ref "CF1") (pin "P$1") (pinfunction "SHIELD_P$1") (pintype "passive"))
      (node (ref "CF1") (pin "P$2") (pinfunction "SHIELD_P$2") (pintype "passive"))
      (node (ref "CF1") (pin "P$3") (pinfunction "SHIELD_P$3") (pintype "passive"))
      (node (ref "CF1") (pin "P$4") (pinfunction "SHIELD_P$4") (pintype "passive"))
      (node (ref "D4") (pin "C") (pinfunction "C_C") (pintype "passive"))
      (node (ref "D6") (pin "C") (pinfunction "C_C") (pintype "passive"))
      (node (ref "J1") (pin "1A") (pinfunction "1A_1A") (pintype "passive"))
      (node (ref "J1") (pin "1B") (pinfunction "1B_1B") (pintype "passive"))
      (node (ref "J1") (pin "3A") (pinfunction "3A_3A") (pintype "passive"))
      (node (ref "J1") (pin "3B") (pinfunction "3B_3B") (pintype "passive"))
      (node (ref "J2") (pin "3") (pinfunction "GND_3") (pintype "passive"))
      (node (ref "J2") (pin "6") (pinfunction "GND_6") (pintype "passive"))
      (node (ref "J2") (pin "9") (pinfunction "GND_9") (pintype "passive"))
      (node (ref "J2") (pin "PAD1") (pinfunction "PAD_PAD1") (pintype "bidirectional"))
      (node (ref "J2") (pin "PAD2") (pinfunction "PAD_PAD2") (pintype "bidirectional"))
      (node (ref "R11") (pin "1") (pinfunction "1_1") (pintype "passive"))
      (node (ref "R12") (pin "1") (pinfunction "1_1") (pintype "passive"))
      (node (ref "R2") (pin "1") (pinfunction "1_1") (pintype "passive"))
      (node (ref "R22") (pin "2") (pinfunction "2_2") (pintype "passive"))
      (node (ref "R24") (pin "2") (pinfunction "2_2") (pintype "passive"))
      (node (ref "R25") (pin "2") (pinfunction "2_2") (pintype "passive"))
      (node (ref "R26") (pin "2") (pinfunction "2_2") (pintype "passive"))
      (node (ref "R27") (pin "2") (pinfunction "2_2") (pintype "passive"))
      (node (ref "R6") (pin "2") (pinfunction "2_2") (pintype "passive"))
      (node (ref "R7") (pin "1") (pinfunction "1_1") (pintype "passive"))
      (node (ref "U1") (pin "2") (pinfunction "GND_2") (pintype "power_in"))
      (node (ref "U10") (pin "11") (pinfunction "PGND_11") (pintype "power_in"))
      (node (ref "U10") (pin "12") (pinfunction "PGND_12") (pintype "power_in"))
      (node (ref "U10") (pin "13") (pinfunction "PGND_13") (pintype "power_in"))
      (node (ref "U10") (pin "14") (pinfunction "PGND_14") (pintype "power_in"))
      (node (ref "U10") (pin "15") (pinfunction "PGND_15") (pintype "power_in"))
      (node (ref "U10") (pin "16") (pinfunction "PGND_16") (pintype "power_in"))
      (node (ref "U10") (pin "17") (pinfunction "PGND_17") (pintype "power_in"))
      (node (ref "U10") (pin "18") (pinfunction "PGND_18") (pintype "power_in"))
      (node (ref "U10") (pin "19") (pinfunction "PGND_19") (pintype "power_in"))
      (node (ref "U10") (pin "7") (pinfunction "GND_7") (pintype "power_in"))
      (node (ref "U11") (pin "5") (pinfunction "GND_5") (pintype "power_in"))
      (node (ref "U12") (pin "2") (pinfunction "GND_2") (pintype "power_in"))
      (node (ref "U2") (pin "2") (pinfunction "ADD0_2") (pintype "input"))
      (node (ref "U2") (pin "5") (pinfunction "GND_5") (pintype "power_in"))
      (node (ref "U3") (pin "5") (pinfunction "GND_5") (pintype "power_in"))
      (node (ref "U4") (pin "1") (pinfunction "A1_1") (pintype "passive"))
      (node (ref "U4") (pin "2") (pinfunction "A0_2") (pintype "passive"))
      (node (ref "U4") (pin "7") (pinfunction "GND_7") (pintype "power_in"))
      (node (ref "U7") (pin "23") (pinfunction "VSS_23") (pintype "power_in"))
      (node (ref "U7") (pin "35") (pinfunction "VSS_35") (pintype "power_in"))
      (node (ref "U7") (pin "47") (pinfunction "VSS_47") (pintype "power_in"))
      (node (ref "U7") (pin "8") (pinfunction "VSSA_8") (pintype "power_in"))
      (node (ref "X1") (pin "2") (pinfunction "SHIELD_2") (pintype "power_in"))
      (node (ref "X1") (pin "4") (pinfunction "SHIELD_4") (pintype "power_in"))
    )
    (net (code "10") (name "LT1618-ENABLE") (class "Default")
      (node (ref "R7") (pin "2") (pinfunction "2_2") (pintype "passive"))
      (node (ref "TP10") (pin "1") (pinfunction "1_1") (pintype "passive"))
      (node (ref "U3") (pin "9") (pinfunction "*SHDN_9") (pintype "input"))
      (node (ref "U7") (pin "11") (pinfunction "PA1_11") (pintype "bidirectional"))
    )
    (net (code "11") (name "LT1618-IADJ") (class "Default")
      (node (ref "R6") (pin "1") (pinfunction "1_1") (pintype "passive"))
      (node (ref "TP2") (pin "1") (pinfunction "1_1") (pintype "passive"))
      (node (ref "U3") (pin "4") (pinfunction "IADJ_4") (pintype "input"))
      (node (ref "U7") (pin "14") (pinfunction "PA4_14") (pintype "bidirectional"))
    )
    (net (code "12") (name "NRESET") (class "Default")
      (node (ref "J2") (pin "10") (pinfunction "NRST_10") (pintype "passive"))
      (node (ref "TP13") (pin "1") (pinfunction "1_1") (pintype "passive"))
      (node (ref "U7") (pin "7") (pinfunction "NRST_7") (pintype "bidirectional"))
    )
    (net (code "13") (name "Net-(C2-Pad1)") (class "Default")
      (node (ref "C2") (pin "1") (pinfunction "1_1") (pintype "passive"))
      (node (ref "R16") (pin "1") (pinfunction "1_1") (pintype "passive"))
    )
    (net (code "14") (name "Net-(CELL1-A1)") (class "Default")
      (node (ref "CELL1") (pin "POS1") (pinfunction "A1_POS1") (pintype "passive"))
      (node (ref "CELL1") (pin "POS2") (pinfunction "A2_POS2") (pintype "passive"))
      (node (ref "CELL2") (pin "NEG1") (pinfunction "C1_NEG1") (pintype "passive"))
      (node (ref "CELL2") (pin "NEG2") (pinfunction "C2_NEG2") (pintype "passive"))
      (node (ref "CELL2") (pin "NEG3") (pinfunction "C3_NEG3") (pintype "passive"))
      (node (ref "CELL2") (pin "NEG4") (pinfunction "C4_NEG4") (pintype "passive"))
    )
    (net (code "15") (name "Net-(CF1-AUX-Pad7)") (class "Default")
      (node (ref "CF1") (pin "7") (pinfunction "AUX_7") (pintype "passive"))
      (node (ref "CF1") (pin "8") (pinfunction "AUX_8") (pintype "passive"))
      (node (ref "TP1") (pin "1") (pinfunction "1_1") (pintype "passive"))
    )
    (net (code "16") (name "Net-(D4-PadA)") (class "Default")
      (node (ref "D4") (pin "A") (pinfunction "A_A") (pintype "passive"))
      (node (ref "R21") (pin "2") (pinfunction "2_2") (pintype "passive"))
    )
    (net (code "17") (name "Net-(D5-ANODE)") (class "Default")
      (node (ref "D5") (pin "A") (pinfunction "ANODE_A") (pintype "passive"))
      (node (ref "L2") (pin "P$2") (pinfunction "2_P$2") (pintype "passive"))
      (node (ref "U3") (pin "7") (pinfunction "SW_7") (pintype "output"))
    )
    (net (code "18") (name "Net-(D6-PadA)") (class "Default")
      (node (ref "D6") (pin "A") (pinfunction "A_A") (pintype "passive"))
      (node (ref "R23") (pin "1") (pinfunction "1_1") (pintype "passive"))
    )
    (net (code "19") (name "Net-(J2-DEBUG-0)") (class "Default")
      (node (ref "J2") (pin "17") (pinfunction "DEBUG-0_17") (pintype "passive"))
      (node (ref "TP17") (pin "1") (pinfunction "1_1") (pintype "passive"))
    )
    (net (code "20") (name "Net-(J2-DEBUG-1)") (class "Default")
      (node (ref "J2") (pin "18") (pinfunction "DEBUG-1_18") (pintype "passive"))
      (node (ref "R15") (pin "2") (pinfunction "2_2") (pintype "passive"))
      (node (ref "TP18") (pin "1") (pinfunction "1_1") (pintype "passive"))
    )
    (net (code "21") (name "Net-(J2-DEBUG-2)") (class "Default")
      (node (ref "J2") (pin "19") (pinfunction "DEBUG-2_19") (pintype "passive"))
      (node (ref "TP19") (pin "1") (pinfunction "1_1") (pintype "passive"))
    )
    (net (code "22") (name "Net-(J2-DEBUG-3)") (class "Default")
      (node (ref "J2") (pin "20") (pinfunction "DEBUG-3_20") (pintype "passive"))
      (node (ref "TP20") (pin "1") (pinfunction "1_1") (pintype "passive"))
    )
    (net (code "23") (name "Net-(J2-SWO)") (class "Default")
      (node (ref "J2") (pin "16") (pinfunction "SWO_16") (pintype "passive"))
      (node (ref "TP21") (pin "1") (pinfunction "1_1") (pintype "passive"))
    )
    (net (code "24") (name "Net-(J2-VBUSP-Pad1)") (class "Default")
      (node (ref "J2") (pin "1") (pinfunction "VBUSP_1") (pintype "passive"))
      (node (ref "J2") (pin "2") (pinfunction "VBUSP_2") (pintype "passive"))
      (node (ref "TP8") (pin "1") (pinfunction "1_1") (pintype "passive"))
    )
    (net (code "25") (name "Net-(L2-1)") (class "Default")
      (node (ref "L2") (pin "P$1") (pinfunction "1_P$1") (pintype "passive"))
      (node (ref "R17") (pin "2") (pinfunction "2_2") (pintype "passive"))
      (node (ref "TP5") (pin "1") (pinfunction "1_1") (pintype "passive"))
      (node (ref "U3") (pin "2") (pinfunction "ISN_2") (pintype "passive"))
      (node (ref "U4") (pin "8") (pinfunction "VBUS_8") (pintype "input"))
      (node (ref "U4") (pin "9") (pinfunction "VIN-_9") (pintype "input"))
    )
    (net (code "26") (name "Net-(Q2A-G)") (class "Default")
      (node (ref "Q2") (pin "1") (pinfunction "G_1") (pintype "passive"))
      (node (ref "Q2") (pin "3") (pinfunction "G_3") (pintype "passive"))
      (node (ref "U12") (pin "5") (pinfunction "GATE_5") (pintype "output"))
    )
    (net (code "27") (name "Net-(Q2A-S)") (class "Default")
      (node (ref "Q2") (pin "2") (pinfunction "S_2") (pintype "passive"))
      (node (ref "Q2") (pin "5") (pinfunction "S_5") (pintype "passive"))
    )
    (net (code "28") (name "Net-(U2-ALERT)") (class "Default")
      (node (ref "TP4") (pin "1") (pinfunction "1_1") (pintype "passive"))
      (node (ref "U2") (pin "6") (pinfunction "ALERT_6") (pintype "output"))
    )
    (net (code "29") (name "Net-(U3-FB)") (class "Default")
      (node (ref "R10") (pin "1") (pinfunction "1_1") (pintype "passive"))
      (node (ref "R12") (pin "2") (pinfunction "2_2") (pintype "passive"))
      (node (ref "U3") (pin "1") (pinfunction "FB_1") (pintype "input"))
    )
    (net (code "30") (name "Net-(U3-VC)") (class "Default")
      (node (ref "R16") (pin "2") (pinfunction "2_2") (pintype "passive"))
      (node (ref "U3") (pin "10") (pinfunction "VC_10") (pintype "passive"))
    )
    (net (code "31") (name "Net-(U4-ALERT)") (class "Default")
      (node (ref "TP24") (pin "1") (pinfunction "1_1") (pintype "passive"))
      (node (ref "U4") (pin "3") (pinfunction "ALERT_3") (pintype "output"))
    )
    (net (code "32") (name "Net-(U7-PA5)") (class "Default")
      (node (ref "TP15") (pin "1") (pinfunction "1_1") (pintype "passive"))
      (node (ref "U7") (pin "15") (pinfunction "PA5_15") (pintype "bidirectional"))
    )
    (net (code "33") (name "Net-(U7-PA6)") (class "Default")
      (node (ref "TP22") (pin "1") (pinfunction "1_1") (pintype "passive"))
      (node (ref "U7") (pin "16") (pinfunction "PA6_16") (pintype "bidirectional"))
    )
    (net (code "34") (name "Net-(U7-PF0-OSC_IN)") (class "Default")
      (node (ref "C28") (pin "1") (pinfunction "1_1") (pintype "passive"))
      (node (ref "U7") (pin "5") (pinfunction "PF0-OSC_IN_5") (pintype "bidirectional"))
      (node (ref "X1") (pin "1") (pinfunction "1_1") (pintype "passive"))
    )
    (net (code "35") (name "Net-(U7-PF1-OSC_OUT)") (class "Default")
      (node (ref "C27") (pin "1") (pinfunction "1_1") (pintype "passive"))
      (node (ref "U7") (pin "6") (pinfunction "PF1-OSC_OUT_6") (pintype "bidirectional"))
      (node (ref "X1") (pin "3") (pinfunction "2_3") (pintype "passive"))
    )
    (net (code "36") (name "Net-(U10-FB)") (class "Default")
      (node (ref "C22") (pin "1") (pinfunction "1_1") (pintype "passive"))
      (node (ref "R1") (pin "1") (pinfunction "1_1") (pintype "passive"))
      (node (ref "R2") (pin "2") (pinfunction "2_2") (pintype "passive"))
      (node (ref "TP27") (pin "1") (pinfunction "1_1") (pintype "passive"))
      (node (ref "U10") (pin "8") (pinfunction "FB_8") (pintype "passive"))
    )
    (net (code "37") (name "Net-(U10-L1)") (class "Default")
      (node (ref "L1") (pin "1") (pinfunction "1_1") (pintype "passive"))
      (node (ref "U10") (pin "1") (pinfunction "L1_1") (pintype "passive"))
    )
    (net (code "38") (name "Net-(U10-L2)") (class "Default")
      (node (ref "L1") (pin "2") (pinfunction "2_2") (pintype "passive"))
      (node (ref "U10") (pin "10") (pinfunction "L2_10") (pintype "passive"))
    )
    (net (code "39") (name "Net-(U10-PG)") (class "Default")
      (node (ref "R9") (pin "1") (pinfunction "1_1") (pintype "passive"))
      (node (ref "TP26") (pin "1") (pinfunction "1_1") (pintype "passive"))
      (node (ref "U10") (pin "5") (pinfunction "PG_5") (pintype "open_collector"))
    )
    (net (code "40") (name "Net-(U10-PS{slash}SYNC)") (class "Default")
      (node (ref "R11") (pin "2") (pinfunction "2_2") (pintype "passive"))
      (node (ref "R13") (pin "1") (pinfunction "1_1") (pintype "passive"))
      (node (ref "TP29") (pin "1") (pinfunction "1_1") (pintype "passive"))
      (node (ref "U10") (pin "4") (pinfunction "PS/SYNC_4") (pintype "input"))
    )
    (net (code "41") (name "Net-(U10-VAUX)") (class "Default")
      (node (ref "C7") (pin "1") (pinfunction "1_1") (pintype "passive"))
      (node (ref "TP28") (pin "1") (pinfunction "1_1") (pintype "passive"))
      (node (ref "U10") (pin "6") (pinfunction "VAUX_6") (pintype "output"))
    )
    (net (code "42") (name "Net-(U10-VIN)") (class "Default")
      (node (ref "C12") (pin "1") (pinfunction "1_1") (pintype "passive"))
      (node (ref "C20") (pin "1") (pinfunction "1_1") (pintype "passive"))
      (node (ref "R13") (pin "2") (pinfunction "2_2") (pintype "passive"))
      (node (ref "R14") (pin "1") (pinfunction "1_1") (pintype "passive"))
      (node (ref "R18") (pin "1") (pinfunction "1_1") (pintype "passive"))
      (node (ref "U10") (pin "2") (pinfunction "VIN_2") (pintype "power_in"))
    )
    (net (code "43") (name "Net-(U11-ALERT)") (class "Default")
      (node (ref "TP30") (pin "1") (pinfunction "1_1") (pintype "passive"))
      (node (ref "U11") (pin "6") (pinfunction "ALERT_6") (pintype "output"))
    )
    (net (code "44") (name "Net-(U12-CTL)") (class "Default")
      (node (ref "Q1") (pin "1") (pinfunction "D_1") (pintype "passive"))
      (node (ref "Q1") (pin "2") (pinfunction "D_2") (pintype "passive"))
      (node (ref "Q1") (pin "5") (pinfunction "D_5") (pintype "passive"))
      (node (ref "Q1") (pin "6") (pinfunction "D_6") (pintype "passive"))
      (node (ref "U12") (pin "3") (pinfunction "CTL_3") (pintype "input"))
    )
    (net (code "45") (name "Net-(U12-STAT)") (class "Default")
      (node (ref "TP16") (pin "1") (pinfunction "1_1") (pintype "passive"))
      (node (ref "U12") (pin "4") (pinfunction "STAT_4") (pintype "open_collector"))
    )
    (net (code "46") (name "PA0") (class "Default")
      (node (ref "R23") (pin "2") (pinfunction "2_2") (pintype "passive"))
      (node (ref "U7") (pin "10") (pinfunction "PA0_10") (pintype "bidirectional"))
    )
    (net (code "47") (name "PA2{slash}USART2_TX") (class "Default")
      (node (ref "J2") (pin "13") (pinfunction "CARD-TX_13") (pintype "passive"))
      (node (ref "U7") (pin "12") (pinfunction "PA2_12") (pintype "bidirectional"))
    )
    (net (code "48") (name "PA3{slash}USART2_RX") (class "Default")
      (node (ref "J2") (pin "12") (pinfunction "CARD-RX_12") (pintype "passive"))
      (node (ref "U7") (pin "13") (pinfunction "PA3_13") (pintype "bidirectional"))
    )
    (net (code "49") (name "SCL") (class "Default")
      (node (ref "R3") (pin "1") (pinfunction "1_1") (pintype "passive"))
      (node (ref "TP31") (pin "1") (pinfunction "1_1") (pintype "passive"))
      (node (ref "U11") (pin "4") (pinfunction "SCL_4") (pintype "input"))
      (node (ref "U2") (pin "4") (pinfunction "SCL_4") (pintype "input"))
      (node (ref "U4") (pin "5") (pinfunction "SCL_5") (pintype "input"))
      (node (ref "U7") (pin "21") (pinfunction "PB10_21") (pintype "bidirectional"))
    )
    (net (code "50") (name "SDA") (class "Default")
      (node (ref "R4") (pin "1") (pinfunction "1_1") (pintype "passive"))
      (node (ref "TP23") (pin "1") (pinfunction "1_1") (pintype "passive"))
      (node (ref "U11") (pin "3") (pinfunction "SDA_3") (pintype "open_collector"))
      (node (ref "U2") (pin "3") (pinfunction "SDA_3") (pintype "open_collector"))
      (node (ref "U4") (pin "4") (pinfunction "SDA_4") (pintype "bidirectional"))
      (node (ref "U7") (pin "22") (pinfunction "PB11_22") (pintype "bidirectional"))
    )
    (net (code "51") (name "SMSN0") (class "Default")
      (node (ref "R24") (pin "1") (pinfunction "1_1") (pintype "passive"))
      (node (ref "U7") (pin "25") (pinfunction "PB12_25") (pintype "bidirectional"))
    )
    (net (code "52") (name "SMSN1") (class "Default")
      (node (ref "R25") (pin "1") (pinfunction "1_1") (pintype "passive"))
      (node (ref "U7") (pin "26") (pinfunction "PB13_26") (pintype "bidirectional"))
    )
    (net (code "53") (name "SMSN2") (class "Default")
      (node (ref "R26") (pin "1") (pinfunction "1_1") (pintype "passive"))
      (node (ref "U7") (pin "27") (pinfunction "PB14_27") (pintype "bidirectional"))
    )
    (net (code "54") (name "SMSN3") (class "Default")
      (node (ref "R27") (pin "1") (pinfunction "1_1") (pintype "passive"))
      (node (ref "U7") (pin "28") (pinfunction "PB15_28") (pintype "bidirectional"))
    )
    (net (code "55") (name "SWCLK") (class "Default")
      (node (ref "J2") (pin "15") (pinfunction "SWCLK_15") (pintype "passive"))
      (node (ref "U7") (pin "37") (pinfunction "PA14-SWCLK_37") (pintype "bidirectional"))
    )
    (net (code "56") (name "SWDIO") (class "Default")
      (node (ref "J2") (pin "14") (pinfunction "SWDIO_14") (pintype "passive"))
      (node (ref "U7") (pin "34") (pinfunction "PA13-SWDIO_34") (pintype "bidirectional"))
    )
    (net (code "57") (name "TPS-VOUT-3.3V") (class "Default")
      (node (ref "C13") (pin "1") (pinfunction "1_1") (pintype "passive"))
      (node (ref "C15") (pin "1") (pinfunction "1_1") (pintype "passive"))
      (node (ref "C19") (pin "1") (pinfunction "1_1") (pintype "passive"))
      (node (ref "C23") (pin "1") (pinfunction "1_1") (pintype "passive"))
      (node (ref "R1") (pin "2") (pinfunction "2_2") (pintype "passive"))
      (node (ref "R20") (pin "2") (pinfunction "2_2") (pintype "passive"))
      (node (ref "R9") (pin "2") (pinfunction "2_2") (pintype "passive"))
      (node (ref "TP6") (pin "1") (pinfunction "1_1") (pintype "passive"))
      (node (ref "U10") (pin "9") (pinfunction "VOUT_9") (pintype "power_in"))
    )
    (net (code "58") (name "VBUS") (class "Default")
      (node (ref "CF1") (pin "5") (pinfunction "VBUS_5") (pintype "passive"))
      (node (ref "CF1") (pin "6") (pinfunction "VBUS_6") (pintype "passive"))
      (node (ref "Q2") (pin "6") (pinfunction "D_6") (pintype "passive"))
      (node (ref "TP14") (pin "1") (pinfunction "1_1") (pintype "passive"))
      (node (ref "U12") (pin "6") (pinfunction "SENSE_6") (pintype "input"))
    )
    (net (code "59") (name "VMPPT") (class "Default")
      (node (ref "C18") (pin "1") (pinfunction "1_1") (pintype "passive"))
      (node (ref "C21") (pin "1") (pinfunction "1_1") (pintype "passive"))
      (node (ref "D5") (pin "K") (pinfunction "CATHODE_K") (pintype "passive"))
      (node (ref "Q1") (pin "4") (pinfunction "S_4") (pintype "passive"))
      (node (ref "Q2") (pin "4") (pinfunction "D_4") (pintype "passive"))
      (node (ref "R10") (pin "2") (pinfunction "2_2") (pintype "passive"))
      (node (ref "R19") (pin "2") (pinfunction "2_2") (pintype "passive"))
      (node (ref "TP12") (pin "1") (pinfunction "1_1") (pintype "passive"))
      (node (ref "U12") (pin "1") (pinfunction "VIN_1") (pintype "power_in"))
    )
    (net (code "60") (name "VSOLAR") (class "Default")
      (node (ref "C14") (pin "1") (pinfunction "1_1") (pintype "passive"))
      (node (ref "C4") (pin "1") (pinfunction "1_1") (pintype "passive"))
      (node (ref "C6") (pin "1") (pinfunction "1_1") (pintype "passive"))
      (node (ref "CELL2") (pin "POS1") (pinfunction "A1_POS1") (pintype "passive"))
      (node (ref "CELL2") (pin "POS2") (pinfunction "A2_POS2") (pintype "passive"))
      (node (ref "R14") (pin "2") (pinfunction "2_2") (pintype "passive"))
      (node (ref "R17") (pin "1") (pinfunction "1_1") (pintype "passive"))
      (node (ref "TP3") (pin "1") (pinfunction "1_1") (pintype "passive"))
      (node (ref "U3") (pin "3") (pinfunction "ISP_3") (pintype "passive"))
      (node (ref "U3") (pin "8") (pinfunction "VIN_8") (pintype "power_in"))
      (node (ref "U4") (pin "10") (pinfunction "VIN+_10") (pintype "input"))
    )
    (net (code "61") (name "unconnected-(J2-DEVICE-D+-Pad4)") (class "Default")
      (node (ref "J2") (pin "4") (pinfunction "DEVICE-D+_4") (pintype "passive"))
    )
    (net (code "62") (name "unconnected-(J2-DEVICE-D--Pad5)") (class "Default")
      (node (ref "J2") (pin "5") (pinfunction "DEVICE-D-_5") (pintype "passive"))
    )
    (net (code "63") (name "unconnected-(J2-HOST-D+-Pad7)") (class "Default")
      (node (ref "J2") (pin "7") (pinfunction "HOST-D+_7") (pintype "passive"))
    )
    (net (code "64") (name "unconnected-(J2-HOST-D--Pad8)") (class "Default")
      (node (ref "J2") (pin "8") (pinfunction "HOST-D-_8") (pintype "passive"))
    )
    (net (code "65") (name "unconnected-(U7-PA7-Pad17)") (class "Default")
      (node (ref "U7") (pin "17") (pinfunction "PA7_17") (pintype "bidirectional"))
    )
    (net (code "66") (name "unconnected-(U7-PA8-Pad29)") (class "Default")
      (node (ref "U7") (pin "29") (pinfunction "PA8_29") (pintype "bidirectional"))
    )
    (net (code "67") (name "unconnected-(U7-PA15-Pad38)") (class "Default")
      (node (ref "U7") (pin "38") (pinfunction "PA15_38") (pintype "bidirectional"))
    )
    (net (code "68") (name "unconnected-(U7-PB0-Pad18)") (class "Default")
      (node (ref "U7") (pin "18") (pinfunction "PB0_18") (pintype "bidirectional"))
    )
    (net (code "69") (name "unconnected-(U7-PB1-Pad19)") (class "Default")
      (node (ref "U7") (pin "19") (pinfunction "PB1_19") (pintype "bidirectional"))
    )
    (net (code "70") (name "unconnected-(U7-PB2-Pad20)") (class "Default")
      (node (ref "U7") (pin "20") (pinfunction "PB2_20") (pintype "bidirectional"))
    )
    (net (code "71") (name "unconnected-(U7-PB3-Pad39)") (class "Default")
      (node (ref "U7") (pin "39") (pinfunction "PB3_39") (pintype "bidirectional"))
    )
    (net (code "72") (name "unconnected-(U7-PB4-Pad40)") (class "Default")
      (node (ref "U7") (pin "40") (pinfunction "PB4_40") (pintype "bidirectional"))
    )
    (net (code "73") (name "unconnected-(U7-PB5-Pad41)") (class "Default")
      (node (ref "U7") (pin "41") (pinfunction "PB5_41") (pintype "bidirectional"))
    )
    (net (code "74") (name "unconnected-(U7-PB6-Pad42)") (class "Default")
      (node (ref "U7") (pin "42") (pinfunction "PB6_42") (pintype "bidirectional"))
    )
    (net (code "75") (name "unconnected-(U7-PB7-Pad43)") (class "Default")
      (node (ref "U7") (pin "43") (pinfunction "PB7_43") (pintype "bidirectional"))
    )
    (net (code "76") (name "unconnected-(U7-PB8-Pad45)") (class "Default")
      (node (ref "U7") (pin "45") (pinfunction "PB8_45") (pintype "bidirectional"))
    )
    (net (code "77") (name "unconnected-(U7-PB9-Pad46)") (class "Default")
      (node (ref "U7") (pin "46") (pinfunction "PB9_46") (pintype "bidirectional"))
    )
    (net (code "78") (name "unconnected-(U7-PC13-Pad2)") (class "Default")
      (node (ref "U7") (pin "2") (pinfunction "PC13_2") (pintype "bidirectional"))
    )
    (net (code "79") (name "unconnected-(U7-PC14-OSC32_IN-Pad3)") (class "Default")
      (node (ref "U7") (pin "3") (pinfunction "PC14-OSC32_IN_3") (pintype "bidirectional"))
    )
    (net (code "80") (name "unconnected-(U7-PC15-OSC32_OUT-Pad4)") (class "Default")
      (node (ref "U7") (pin "4") (pinfunction "PC15-OSC32_OUT_4") (pintype "bidirectional"))
    )
    (net (code "81") (name "~{SHDN-3.3V}") (class "Default")
      (node (ref "D1") (pin "A") (pinfunction "A_A") (pintype "passive"))
      (node (ref "R18") (pin "2") (pinfunction "2_2") (pintype "passive"))
      (node (ref "TP9") (pin "1") (pinfunction "1_1") (pintype "passive"))
      (node (ref "U10") (pin "3") (pinfunction "EN_3") (pintype "input"))
    )
    (net (code "82") (name "~{SHDN-OUPUT}") (class "Default")
      (node (ref "D3") (pin "A") (pinfunction "A_A") (pintype "passive"))
      (node (ref "Q1") (pin "3") (pinfunction "G_3") (pintype "passive"))
      (node (ref "R19") (pin "1") (pinfunction "1_1") (pintype "passive"))
      (node (ref "TP25") (pin "1") (pinfunction "1_1") (pintype "passive"))
    )
    (net (code "83") (name "~{SHUTDOWN}") (class "Default")
      (node (ref "CF1") (pin "1") (pinfunction "~{SD}_1") (pintype "passive"))
      (node (ref "CF1") (pin "2") (pinfunction "~{SD}_2") (pintype "passive"))
      (node (ref "D1") (pin "C") (pinfunction "C_C") (pintype "passive"))
      (node (ref "D3") (pin "C") (pinfunction "C_C") (pintype "passive"))
      (node (ref "J1") (pin "2A") (pinfunction "2A_2A") (pintype "passive"))
      (node (ref "J1") (pin "2B") (pinfunction "2B_2B") (pintype "passive"))
      (node (ref "J1") (pin "4A") (pinfunction "4A_4A") (pintype "passive"))
      (node (ref "J1") (pin "4B") (pinfunction "4B_4B") (pintype "passive"))
      (node (ref "TP11") (pin "1") (pinfunction "1_1") (pintype "passive"))
    )
  )
)
